# STM32.net
KiCad netlist of a schematic drawn in Altium Designer
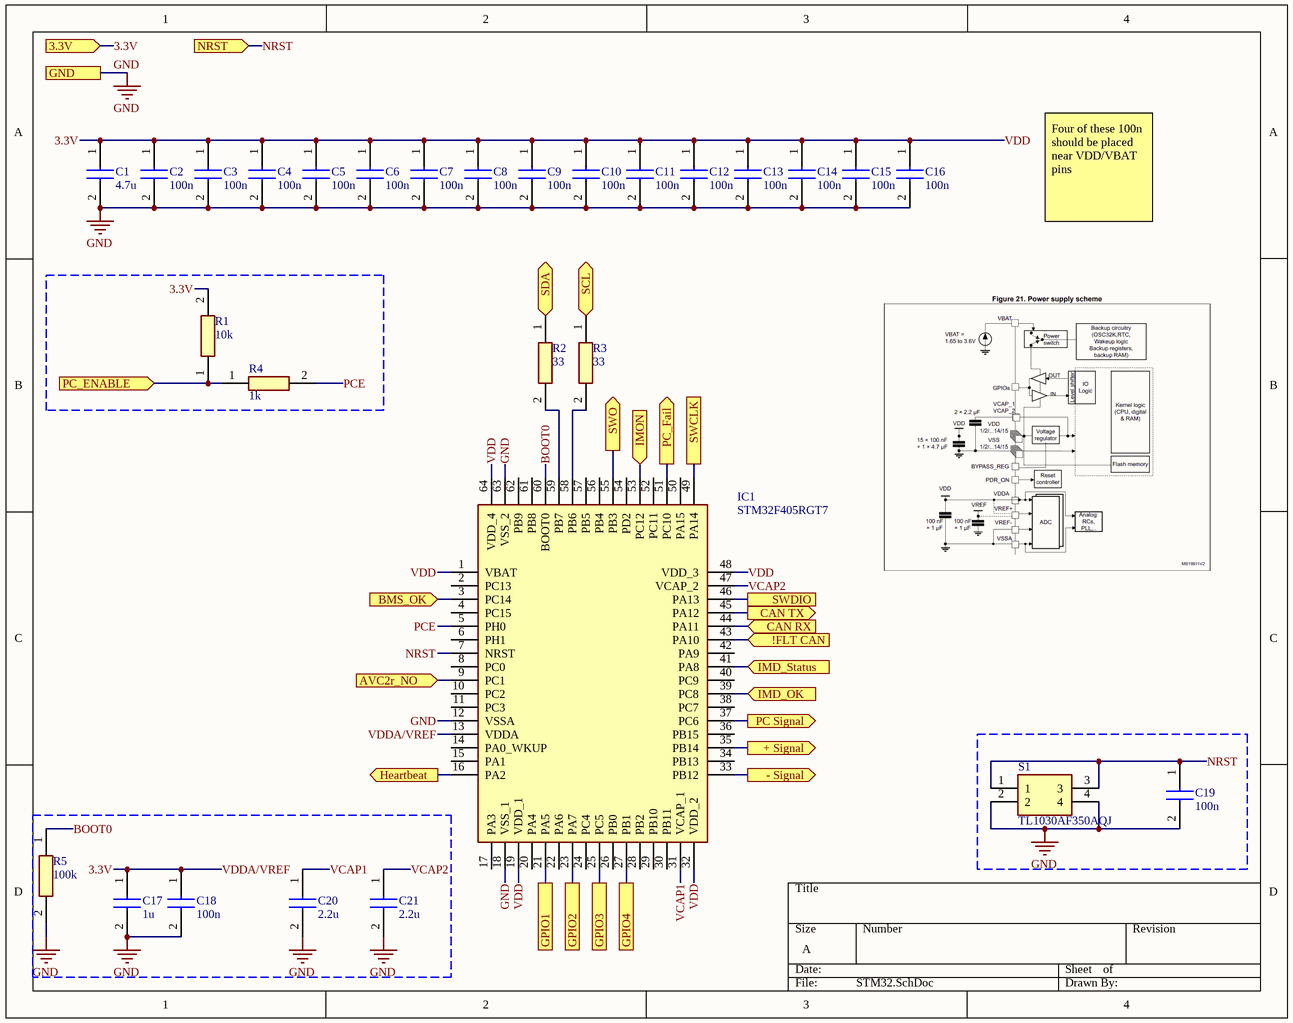
[diagram p0: STM32.SchDoc]

(export (version "E")
  (design (tool "Eeschema 10.0.6"))
  (components
    (comp (ref "C1")
      (value "4.7u")
      (footprint "SamacSys:CAPC2012X145N")
      (description "Capacitor")
      (fields
        (field (name "MANUFACTURER_PART_NUMBER") "GRM21BR61H475ME51L")
        (field (name "MOUSER PART NUMBER") "81-GRM21BR61H475M51L")
      )
      (libsource (lib "*") (part "GRM21BR61H475ME51L"))
    )
    (comp (ref "C2")
      (value "100n")
      (footprint "SamacSys:CAPC1608X90N")
      (description "Capacitor")
      (fields
        (field (name "MANUFACTURER_PART_NUMBER") "06035C104J4Z2A")
        (field (name "MOUSER PART NUMBER") "581-06035C104J4Z2A")
      )
      (libsource (lib "*") (part "06035C104J4Z2A"))
    )
    (comp (ref "C3")
      (value "100n")
      (footprint "SamacSys:CAPC1608X90N")
      (description "Capacitor")
      (fields
        (field (name "MANUFACTURER_PART_NUMBER") "06035C104J4Z2A")
        (field (name "MOUSER PART NUMBER") "581-06035C104J4Z2A")
      )
      (libsource (lib "*") (part "06035C104J4Z2A"))
    )
    (comp (ref "C4")
      (value "100n")
      (footprint "SamacSys:CAPC1608X90N")
      (description "Capacitor")
      (fields
        (field (name "MANUFACTURER_PART_NUMBER") "06035C104J4Z2A")
        (field (name "MOUSER PART NUMBER") "581-06035C104J4Z2A")
      )
      (libsource (lib "*") (part "06035C104J4Z2A"))
    )
    (comp (ref "C5")
      (value "100n")
      (footprint "SamacSys:CAPC1608X90N")
      (description "Capacitor")
      (fields
        (field (name "MANUFACTURER_PART_NUMBER") "06035C104J4Z2A")
        (field (name "MOUSER PART NUMBER") "581-06035C104J4Z2A")
      )
      (libsource (lib "*") (part "06035C104J4Z2A"))
    )
    (comp (ref "C6")
      (value "100n")
      (footprint "SamacSys:CAPC1608X90N")
      (description "Capacitor")
      (fields
        (field (name "MANUFACTURER_PART_NUMBER") "06035C104J4Z2A")
        (field (name "MOUSER PART NUMBER") "581-06035C104J4Z2A")
      )
      (libsource (lib "*") (part "06035C104J4Z2A"))
    )
    (comp (ref "C7")
      (value "100n")
      (footprint "SamacSys:CAPC1608X90N")
      (description "Capacitor")
      (fields
        (field (name "MANUFACTURER_PART_NUMBER") "06035C104J4Z2A")
        (field (name "MOUSER PART NUMBER") "581-06035C104J4Z2A")
      )
      (libsource (lib "*") (part "06035C104J4Z2A"))
    )
    (comp (ref "C8")
      (value "100n")
      (footprint "SamacSys:CAPC1608X90N")
      (description "Capacitor")
      (fields
        (field (name "MANUFACTURER_PART_NUMBER") "06035C104J4Z2A")
        (field (name "MOUSER PART NUMBER") "581-06035C104J4Z2A")
      )
      (libsource (lib "*") (part "06035C104J4Z2A"))
    )
    (comp (ref "C9")
      (value "100n")
      (footprint "SamacSys:CAPC1608X90N")
      (description "Capacitor")
      (fields
        (field (name "MANUFACTURER_PART_NUMBER") "06035C104J4Z2A")
        (field (name "MOUSER PART NUMBER") "581-06035C104J4Z2A")
      )
      (libsource (lib "*") (part "06035C104J4Z2A"))
    )
    (comp (ref "C10")
      (value "100n")
      (footprint "SamacSys:CAPC1608X90N")
      (description "Capacitor")
      (fields
        (field (name "MANUFACTURER_PART_NUMBER") "06035C104J4Z2A")
        (field (name "MOUSER PART NUMBER") "581-06035C104J4Z2A")
      )
      (libsource (lib "*") (part "06035C104J4Z2A"))
    )
    (comp (ref "C11")
      (value "100n")
      (footprint "SamacSys:CAPC1608X90N")
      (description "Capacitor")
      (fields
        (field (name "MANUFACTURER_PART_NUMBER") "06035C104J4Z2A")
        (field (name "MOUSER PART NUMBER") "581-06035C104J4Z2A")
      )
      (libsource (lib "*") (part "06035C104J4Z2A"))
    )
    (comp (ref "C12")
      (value "100n")
      (footprint "SamacSys:CAPC1608X90N")
      (description "Capacitor")
      (fields
        (field (name "MANUFACTURER_PART_NUMBER") "06035C104J4Z2A")
        (field (name "MOUSER PART NUMBER") "581-06035C104J4Z2A")
      )
      (libsource (lib "*") (part "06035C104J4Z2A"))
    )
    (comp (ref "C13")
      (value "100n")
      (footprint "SamacSys:CAPC1608X90N")
      (description "Capacitor")
      (fields
        (field (name "MANUFACTURER_PART_NUMBER") "06035C104J4Z2A")
        (field (name "MOUSER PART NUMBER") "581-06035C104J4Z2A")
      )
      (libsource (lib "*") (part "06035C104J4Z2A"))
    )
    (comp (ref "C14")
      (value "100n")
      (footprint "SamacSys:CAPC1608X90N")
      (description "Capacitor")
      (fields
        (field (name "MANUFACTURER_PART_NUMBER") "06035C104J4Z2A")
        (field (name "MOUSER PART NUMBER") "581-06035C104J4Z2A")
      )
      (libsource (lib "*") (part "06035C104J4Z2A"))
    )
    (comp (ref "C15")
      (value "100n")
      (footprint "SamacSys:CAPC1608X90N")
      (description "Capacitor")
      (fields
        (field (name "MANUFACTURER_PART_NUMBER") "06035C104J4Z2A")
        (field (name "MOUSER PART NUMBER") "581-06035C104J4Z2A")
      )
      (libsource (lib "*") (part "06035C104J4Z2A"))
    )
    (comp (ref "C16")
      (value "100n")
      (footprint "SamacSys:CAPC1608X90N")
      (description "Capacitor")
      (fields
        (field (name "MANUFACTURER_PART_NUMBER") "06035C104J4Z2A")
        (field (name "MOUSER PART NUMBER") "581-06035C104J4Z2A")
      )
      (libsource (lib "*") (part "06035C104J4Z2A"))
    )
    (comp (ref "C17")
      (value "1u")
      (footprint "SamacSys:CAPC1608X95N")
      (description "Capacitor")
      (fields
        (field (name "MANUFACTURER_PART_NUMBER") "UMK107AB7105KA-T")
        (field (name "MOUSER PART NUMBER") "963-UMK107AB7105KA-T")
      )
      (libsource (lib "*") (part "UMK107AB7105KA-T"))
    )
    (comp (ref "C18")
      (value "100n")
      (footprint "SamacSys:CAPC1608X90N")
      (description "Capacitor")
      (fields
        (field (name "MANUFACTURER_PART_NUMBER") "06035C104J4Z2A")
        (field (name "MOUSER PART NUMBER") "581-06035C104J4Z2A")
      )
      (libsource (lib "*") (part "06035C104J4Z2A"))
    )
    (comp (ref "C19")
      (value "100n")
      (footprint "SamacSys:CAPC1608X90N")
      (description "Capacitor")
      (fields
        (field (name "MANUFACTURER_PART_NUMBER") "06035C104J4Z2A")
        (field (name "MOUSER PART NUMBER") "581-06035C104J4Z2A")
      )
      (libsource (lib "*") (part "06035C104J4Z2A"))
    )
    (comp (ref "C20")
      (value "2.2u")
      (footprint "SamacSys:MBASx168")
      (description "Capacitor")
      (fields (field (name "MANUFACTURER_PART_NUMBER") "MBASL168SB5225KTNA01"))
      (libsource (lib "*") (part "MBASL168SB5225KTNA01"))
    )
    (comp (ref "C21")
      (value "2.2u")
      (footprint "SamacSys:MBASx168")
      (description "Capacitor")
      (fields (field (name "MANUFACTURER_PART_NUMBER") "MBASL168SB5225KTNA01"))
      (libsource (lib "*") (part "MBASL168SB5225KTNA01"))
    )
    (comp (ref "IC1")
      (value "STM32F405RGT7")
      (footprint "SamacSys:QFP50P1200X1200X160-64N")
      (description "Integrated Circuit")
      (fields (field (name "MOUSER PART NUMBER") "511-STM32F405RGT7"))
      (libsource (lib "*") (part "STM32F405RGT7"))
    )
    (comp (ref "R1")
      (value "10k")
      (footprint "SamacSys:RESC1608X55N")
      (description "Resistor")
      (fields
        (field (name "MANUFACTURER_PART_NUMBER") "CRGCQ0603F10K")
        (field (name "MOUSER PART NUMBER") "279-CRGCQ0603F10K")
      )
      (libsource (lib "*") (part "CRGCQ0603F10K"))
    )
    (comp (ref "R2")
      (value "33")
      (footprint "SamacSys:RESC1608X50N")
      (description "Resistor")
      (fields
        (field (name "MANUFACTURER_PART_NUMBER") "CRCW060333R0JNEC")
        (field (name "MOUSER PART NUMBER") "71-CRCW060333R0JNEC")
      )
      (libsource (lib "*") (part "CRCW060333R0JNEC"))
    )
    (comp (ref "R3")
      (value "33")
      (footprint "SamacSys:RESC1608X50N")
      (description "Resistor")
      (fields
        (field (name "MANUFACTURER_PART_NUMBER") "CRCW060333R0JNEC")
        (field (name "MOUSER PART NUMBER") "71-CRCW060333R0JNEC")
      )
      (libsource (lib "*") (part "CRCW060333R0JNEC"))
    )
    (comp (ref "R4")
      (value "1k")
      (footprint "SamacSys:RESC1608X55N")
      (description "Resistor")
      (fields
        (field (name "MANUFACTURER_PART_NUMBER") "RMCF0603JT1K00")
        (field (name "MOUSER PART NUMBER") "708-RMCF0603JT1K00")
      )
      (libsource (lib "*") (part "RMCF0603JT1K00"))
    )
    (comp (ref "R5")
      (value "100k")
      (footprint "SamacSys:RESC1608X55N")
      (description "Resistor")
      (fields
        (field (name "MANUFACTURER_PART_NUMBER") "CR0603-JW-104ELF")
        (field (name "MOUSER PART NUMBER") "652-CR0603-JW-104ELF")
      )
      (libsource (lib "*") (part "CR0603-JW-104ELF"))
    )
    (comp (ref "S1")
      (value "TL1030AF350AQJ")
      (footprint "SamacSys:TL1030AF350AQJ")
      (description "Switch")
      (fields (field (name "MOUSER PART NUMBER") "612-TL1030AF350AQJ"))
      (libsource (lib "SamacSys") (part "TL1030AF350AQJ"))
    )
  )
  (nets
    (net (code "1") (name "/!FLT CAN") (class "Default")
      (node (ref "IC1") (pin "43") (pinfunction "PA10_43") (pintype "passive"))
    )
    (net (code "2") (name "/+ Signal") (class "Default")
      (node (ref "IC1") (pin "35") (pinfunction "PB14_35") (pintype "passive"))
    )
    (net (code "3") (name "/- Signal") (class "Default")
      (node (ref "IC1") (pin "33") (pinfunction "PB12_33") (pintype "passive"))
    )
    (net (code "4") (name "/3.3V") (class "Default")
      (node (ref "C1") (pin "1") (pinfunction "1_1") (pintype "passive"))
      (node (ref "C10") (pin "1") (pinfunction "1_1") (pintype "passive"))
      (node (ref "C11") (pin "1") (pinfunction "1_1") (pintype "passive"))
      (node (ref "C12") (pin "1") (pinfunction "1_1") (pintype "passive"))
      (node (ref "C13") (pin "1") (pinfunction "1_1") (pintype "passive"))
      (node (ref "C14") (pin "1") (pinfunction "1_1") (pintype "passive"))
      (node (ref "C15") (pin "1") (pinfunction "1_1") (pintype "passive"))
      (node (ref "C16") (pin "1") (pinfunction "1_1") (pintype "passive"))
      (node (ref "C17") (pin "1") (pinfunction "1_1") (pintype "passive"))
      (node (ref "C18") (pin "1") (pinfunction "1_1") (pintype "passive"))
      (node (ref "C2") (pin "1") (pinfunction "1_1") (pintype "passive"))
      (node (ref "C3") (pin "1") (pinfunction "1_1") (pintype "passive"))
      (node (ref "C4") (pin "1") (pinfunction "1_1") (pintype "passive"))
      (node (ref "C5") (pin "1") (pinfunction "1_1") (pintype "passive"))
      (node (ref "C6") (pin "1") (pinfunction "1_1") (pintype "passive"))
      (node (ref "C7") (pin "1") (pinfunction "1_1") (pintype "passive"))
      (node (ref "C8") (pin "1") (pinfunction "1_1") (pintype "passive"))
      (node (ref "C9") (pin "1") (pinfunction "1_1") (pintype "passive"))
      (node (ref "IC1") (pin "1") (pinfunction "VBAT_1") (pintype "passive"))
      (node (ref "IC1") (pin "13") (pinfunction "VDDA_13") (pintype "passive"))
      (node (ref "IC1") (pin "19") (pinfunction "VDD_1_19") (pintype "passive"))
      (node (ref "IC1") (pin "32") (pinfunction "VDD_2_32") (pintype "passive"))
      (node (ref "IC1") (pin "48") (pinfunction "VDD_3_48") (pintype "passive"))
      (node (ref "IC1") (pin "64") (pinfunction "VDD_4_64") (pintype "passive"))
      (node (ref "R1") (pin "2") (pinfunction "2_2") (pintype "passive"))
    )
    (net (code "5") (name "/AVC2r_NO") (class "Default")
      (node (ref "IC1") (pin "9") (pinfunction "PC1_9") (pintype "passive"))
    )
    (net (code "6") (name "/BMS_OK") (class "Default")
      (node (ref "IC1") (pin "3") (pinfunction "PC14_3") (pintype "passive"))
    )
    (net (code "7") (name "/BOOT0") (class "Default")
      (node (ref "IC1") (pin "60") (pinfunction "BOOT0_60") (pintype "passive"))
      (node (ref "R5") (pin "1") (pinfunction "1_1") (pintype "passive"))
    )
    (net (code "8") (name "/CAN RX") (class "Default")
      (node (ref "IC1") (pin "44") (pinfunction "PA11_44") (pintype "passive"))
    )
    (net (code "9") (name "/CAN TX") (class "Default")
      (node (ref "IC1") (pin "45") (pinfunction "PA12_45") (pintype "passive"))
    )
    (net (code "10") (name "/GPIO1") (class "Default")
      (node (ref "IC1") (pin "21") (pinfunction "PA5_21") (pintype "passive"))
    )
    (net (code "11") (name "/GPIO2") (class "Default")
      (node (ref "IC1") (pin "23") (pinfunction "PA7_23") (pintype "passive"))
    )
    (net (code "12") (name "/GPIO3") (class "Default")
      (node (ref "IC1") (pin "25") (pinfunction "PC5_25") (pintype "passive"))
    )
    (net (code "13") (name "/GPIO4") (class "Default")
      (node (ref "IC1") (pin "27") (pinfunction "PB1_27") (pintype "passive"))
    )
    (net (code "14") (name "/Heartbeat") (class "Default")
      (node (ref "IC1") (pin "16") (pinfunction "PA2_16") (pintype "passive"))
    )
    (net (code "15") (name "/IMD_OK") (class "Default")
      (node (ref "IC1") (pin "39") (pinfunction "PC8_39") (pintype "passive"))
    )
    (net (code "16") (name "/IMD_Status") (class "Default")
      (node (ref "IC1") (pin "41") (pinfunction "PA8_41") (pintype "passive"))
    )
    (net (code "17") (name "/IMON") (class "Default")
      (node (ref "IC1") (pin "53") (pinfunction "PC12_53") (pintype "passive"))
    )
    (net (code "18") (name "/NRST") (class "Default")
      (node (ref "C19") (pin "1") (pinfunction "1_1") (pintype "passive"))
      (node (ref "IC1") (pin "7") (pinfunction "NRST_7") (pintype "passive"))
      (node (ref "S1") (pin "1") (pinfunction "1_1") (pintype "passive"))
      (node (ref "S1") (pin "3") (pinfunction "3_3") (pintype "passive"))
    )
    (net (code "19") (name "/PC Signal") (class "Default")
      (node (ref "IC1") (pin "37") (pinfunction "PC6_37") (pintype "passive"))
    )
    (net (code "20") (name "/PCE") (class "Default")
      (node (ref "IC1") (pin "5") (pinfunction "PH0_5") (pintype "passive"))
      (node (ref "R4") (pin "2") (pinfunction "2_2") (pintype "passive"))
    )
    (net (code "21") (name "/PC_ENABLE") (class "Default")
      (node (ref "R1") (pin "1") (pinfunction "1_1") (pintype "passive"))
      (node (ref "R4") (pin "1") (pinfunction "1_1") (pintype "passive"))
    )
    (net (code "22") (name "/PC_Fail") (class "Default")
      (node (ref "IC1") (pin "51") (pinfunction "PC10_51") (pintype "passive"))
    )
    (net (code "23") (name "/SCL") (class "Default")
      (node (ref "R3") (pin "1") (pinfunction "1_1") (pintype "passive"))
    )
    (net (code "24") (name "/SDA") (class "Default")
      (node (ref "R2") (pin "1") (pinfunction "1_1") (pintype "passive"))
    )
    (net (code "25") (name "/SWCLK") (class "Default")
      (node (ref "IC1") (pin "49") (pinfunction "PA14_49") (pintype "passive"))
    )
    (net (code "26") (name "/SWDIO") (class "Default")
      (node (ref "IC1") (pin "46") (pinfunction "PA13_46") (pintype "passive"))
    )
    (net (code "27") (name "/SWO") (class "Default")
      (node (ref "IC1") (pin "55") (pinfunction "PB3_55") (pintype "passive"))
    )
    (net (code "28") (name "/VCAP1") (class "Default")
      (node (ref "C20") (pin "1") (pinfunction "1_1") (pintype "passive"))
      (node (ref "IC1") (pin "31") (pinfunction "VCAP_1_31") (pintype "passive"))
    )
    (net (code "29") (name "/VCAP2") (class "Default")
      (node (ref "C21") (pin "1") (pinfunction "1_1") (pintype "passive"))
      (node (ref "IC1") (pin "47") (pinfunction "VCAP_2_47") (pintype "passive"))
    )
    (net (code "30") (name "GND") (class "Default")
      (node (ref "C1") (pin "2") (pinfunction "2_2") (pintype "passive"))
      (node (ref "C10") (pin "2") (pinfunction "2_2") (pintype "passive"))
      (node (ref "C11") (pin "2") (pinfunction "2_2") (pintype "passive"))
      (node (ref "C12") (pin "2") (pinfunction "2_2") (pintype "passive"))
      (node (ref "C13") (pin "2") (pinfunction "2_2") (pintype "passive"))
      (node (ref "C14") (pin "2") (pinfunction "2_2") (pintype "passive"))
      (node (ref "C15") (pin "2") (pinfunction "2_2") (pintype "passive"))
      (node (ref "C16") (pin "2") (pinfunction "2_2") (pintype "passive"))
      (node (ref "C17") (pin "2") (pinfunction "2_2") (pintype "passive"))
      (node (ref "C18") (pin "2") (pinfunction "2_2") (pintype "passive"))
      (node (ref "C19") (pin "2") (pinfunction "2_2") (pintype "passive"))
      (node (ref "C2") (pin "2") (pinfunction "2_2") (pintype "passive"))
      (node (ref "C20") (pin "2") (pinfunction "2_2") (pintype "passive"))
      (node (ref "C21") (pin "2") (pinfunction "2_2") (pintype "passive"))
      (node (ref "C3") (pin "2") (pinfunction "2_2") (pintype "passive"))
      (node (ref "C4") (pin "2") (pinfunction "2_2") (pintype "passive"))
      (node (ref "C5") (pin "2") (pinfunction "2_2") (pintype "passive"))
      (node (ref "C6") (pin "2") (pinfunction "2_2") (pintype "passive"))
      (node (ref "C7") (pin "2") (pinfunction "2_2") (pintype "passive"))
      (node (ref "C8") (pin "2") (pinfunction "2_2") (pintype "passive"))
      (node (ref "C9") (pin "2") (pinfunction "2_2") (pintype "passive"))
      (node (ref "IC1") (pin "12") (pinfunction "VSSA_12") (pintype "passive"))
      (node (ref "IC1") (pin "18") (pinfunction "VSS_1_18") (pintype "passive"))
      (node (ref "IC1") (pin "63") (pinfunction "VSS_2_63") (pintype "passive"))
      (node (ref "R5") (pin "2") (pinfunction "2_2") (pintype "passive"))
      (node (ref "S1") (pin "2") (pinfunction "2_2") (pintype "passive"))
      (node (ref "S1") (pin "4") (pinfunction "4_4") (pintype "passive"))
    )
    (net (code "31") (name "Net-(IC1-PB6)") (class "Default")
      (node (ref "IC1") (pin "58") (pinfunction "PB6_58") (pintype "passive"))
      (node (ref "R3") (pin "2") (pinfunction "2_2") (pintype "passive"))
    )
    (net (code "32") (name "Net-(IC1-PB7)") (class "Default")
      (node (ref "IC1") (pin "59") (pinfunction "PB7_59") (pintype "passive"))
      (node (ref "R2") (pin "2") (pinfunction "2_2") (pintype "passive"))
    )
    (net (code "33") (name "unconnected-(IC1-PA0_WKUP-Pad14)") (class "Default")
      (node (ref "IC1") (pin "14") (pinfunction "PA0_WKUP_14") (pintype "passive"))
    )
    (net (code "34") (name "unconnected-(IC1-PA1-Pad15)") (class "Default")
      (node (ref "IC1") (pin "15") (pinfunction "PA1_15") (pintype "passive"))
    )
    (net (code "35") (name "unconnected-(IC1-PA3-Pad17)") (class "Default")
      (node (ref "IC1") (pin "17") (pinfunction "PA3_17") (pintype "passive"))
    )
    (net (code "36") (name "unconnected-(IC1-PA4-Pad20)") (class "Default")
      (node (ref "IC1") (pin "20") (pinfunction "PA4_20") (pintype "passive"))
    )
    (net (code "37") (name "unconnected-(IC1-PA6-Pad22)") (class "Default")
      (node (ref "IC1") (pin "22") (pinfunction "PA6_22") (pintype "passive"))
    )
    (net (code "38") (name "unconnected-(IC1-PA9-Pad42)") (class "Default")
      (node (ref "IC1") (pin "42") (pinfunction "PA9_42") (pintype "passive"))
    )
    (net (code "39") (name "unconnected-(IC1-PA15-Pad50)") (class "Default")
      (node (ref "IC1") (pin "50") (pinfunction "PA15_50") (pintype "passive"))
    )
    (net (code "40") (name "unconnected-(IC1-PB0-Pad26)") (class "Default")
      (node (ref "IC1") (pin "26") (pinfunction "PB0_26") (pintype "passive"))
    )
    (net (code "41") (name "unconnected-(IC1-PB2-Pad28)") (class "Default")
      (node (ref "IC1") (pin "28") (pinfunction "PB2_28") (pintype "passive"))
    )
    (net (code "42") (name "unconnected-(IC1-PB4-Pad56)") (class "Default")
      (node (ref "IC1") (pin "56") (pinfunction "PB4_56") (pintype "passive"))
    )
    (net (code "43") (name "unconnected-(IC1-PB5-Pad57)") (class "Default")
      (node (ref "IC1") (pin "57") (pinfunction "PB5_57") (pintype "passive"))
    )
    (net (code "44") (name "unconnected-(IC1-PB8-Pad61)") (class "Default")
      (node (ref "IC1") (pin "61") (pinfunction "PB8_61") (pintype "passive"))
    )
    (net (code "45") (name "unconnected-(IC1-PB9-Pad62)") (class "Default")
      (node (ref "IC1") (pin "62") (pinfunction "PB9_62") (pintype "passive"))
    )
    (net (code "46") (name "unconnected-(IC1-PB10-Pad29)") (class "Default")
      (node (ref "IC1") (pin "29") (pinfunction "PB10_29") (pintype "passive"))
    )
    (net (code "47") (name "unconnected-(IC1-PB11-Pad30)") (class "Default")
      (node (ref "IC1") (pin "30") (pinfunction "PB11_30") (pintype "passive"))
    )
    (net (code "48") (name "unconnected-(IC1-PB13-Pad34)") (class "Default")
      (node (ref "IC1") (pin "34") (pinfunction "PB13_34") (pintype "passive"))
    )
    (net (code "49") (name "unconnected-(IC1-PB15-Pad36)") (class "Default")
      (node (ref "IC1") (pin "36") (pinfunction "PB15_36") (pintype "passive"))
    )
    (net (code "50") (name "unconnected-(IC1-PC0-Pad8)") (class "Default")
      (node (ref "IC1") (pin "8") (pinfunction "PC0_8") (pintype "passive"))
    )
    (net (code "51") (name "unconnected-(IC1-PC2-Pad10)") (class "Default")
      (node (ref "IC1") (pin "10") (pinfunction "PC2_10") (pintype "passive"))
    )
    (net (code "52") (name "unconnected-(IC1-PC3-Pad11)") (class "Default")
      (node (ref "IC1") (pin "11") (pinfunction "PC3_11") (pintype "passive"))
    )
    (net (code "53") (name "unconnected-(IC1-PC4-Pad24)") (class "Default")
      (node (ref "IC1") (pin "24") (pinfunction "PC4_24") (pintype "passive"))
    )
    (net (code "54") (name "unconnected-(IC1-PC7-Pad38)") (class "Default")
      (node (ref "IC1") (pin "38") (pinfunction "PC7_38") (pintype "passive"))
    )
    (net (code "55") (name "unconnected-(IC1-PC9-Pad40)") (class "Default")
      (node (ref "IC1") (pin "40") (pinfunction "PC9_40") (pintype "passive"))
    )
    (net (code "56") (name "unconnected-(IC1-PC11-Pad52)") (class "Default")
      (node (ref "IC1") (pin "52") (pinfunction "PC11_52") (pintype "passive"))
    )
    (net (code "57") (name "unconnected-(IC1-PC13-Pad2)") (class "Default")
      (node (ref "IC1") (pin "2") (pinfunction "PC13_2") (pintype "passive"))
    )
    (net (code "58") (name "unconnected-(IC1-PC15-Pad4)") (class "Default")
      (node (ref "IC1") (pin "4") (pinfunction "PC15_4") (pintype "passive"))
    )
    (net (code "59") (name "unconnected-(IC1-PD2-Pad54)") (class "Default")
      (node (ref "IC1") (pin "54") (pinfunction "PD2_54") (pintype "passive"))
    )
    (net (code "60") (name "unconnected-(IC1-PH1-Pad6)") (class "Default")
      (node (ref "IC1") (pin "6") (pinfunction "PH1_6") (pintype "passive"))
    )
  )
)
